# AMC_Connector.net
KiCad netlist of a schematic drawn in Altium Designer
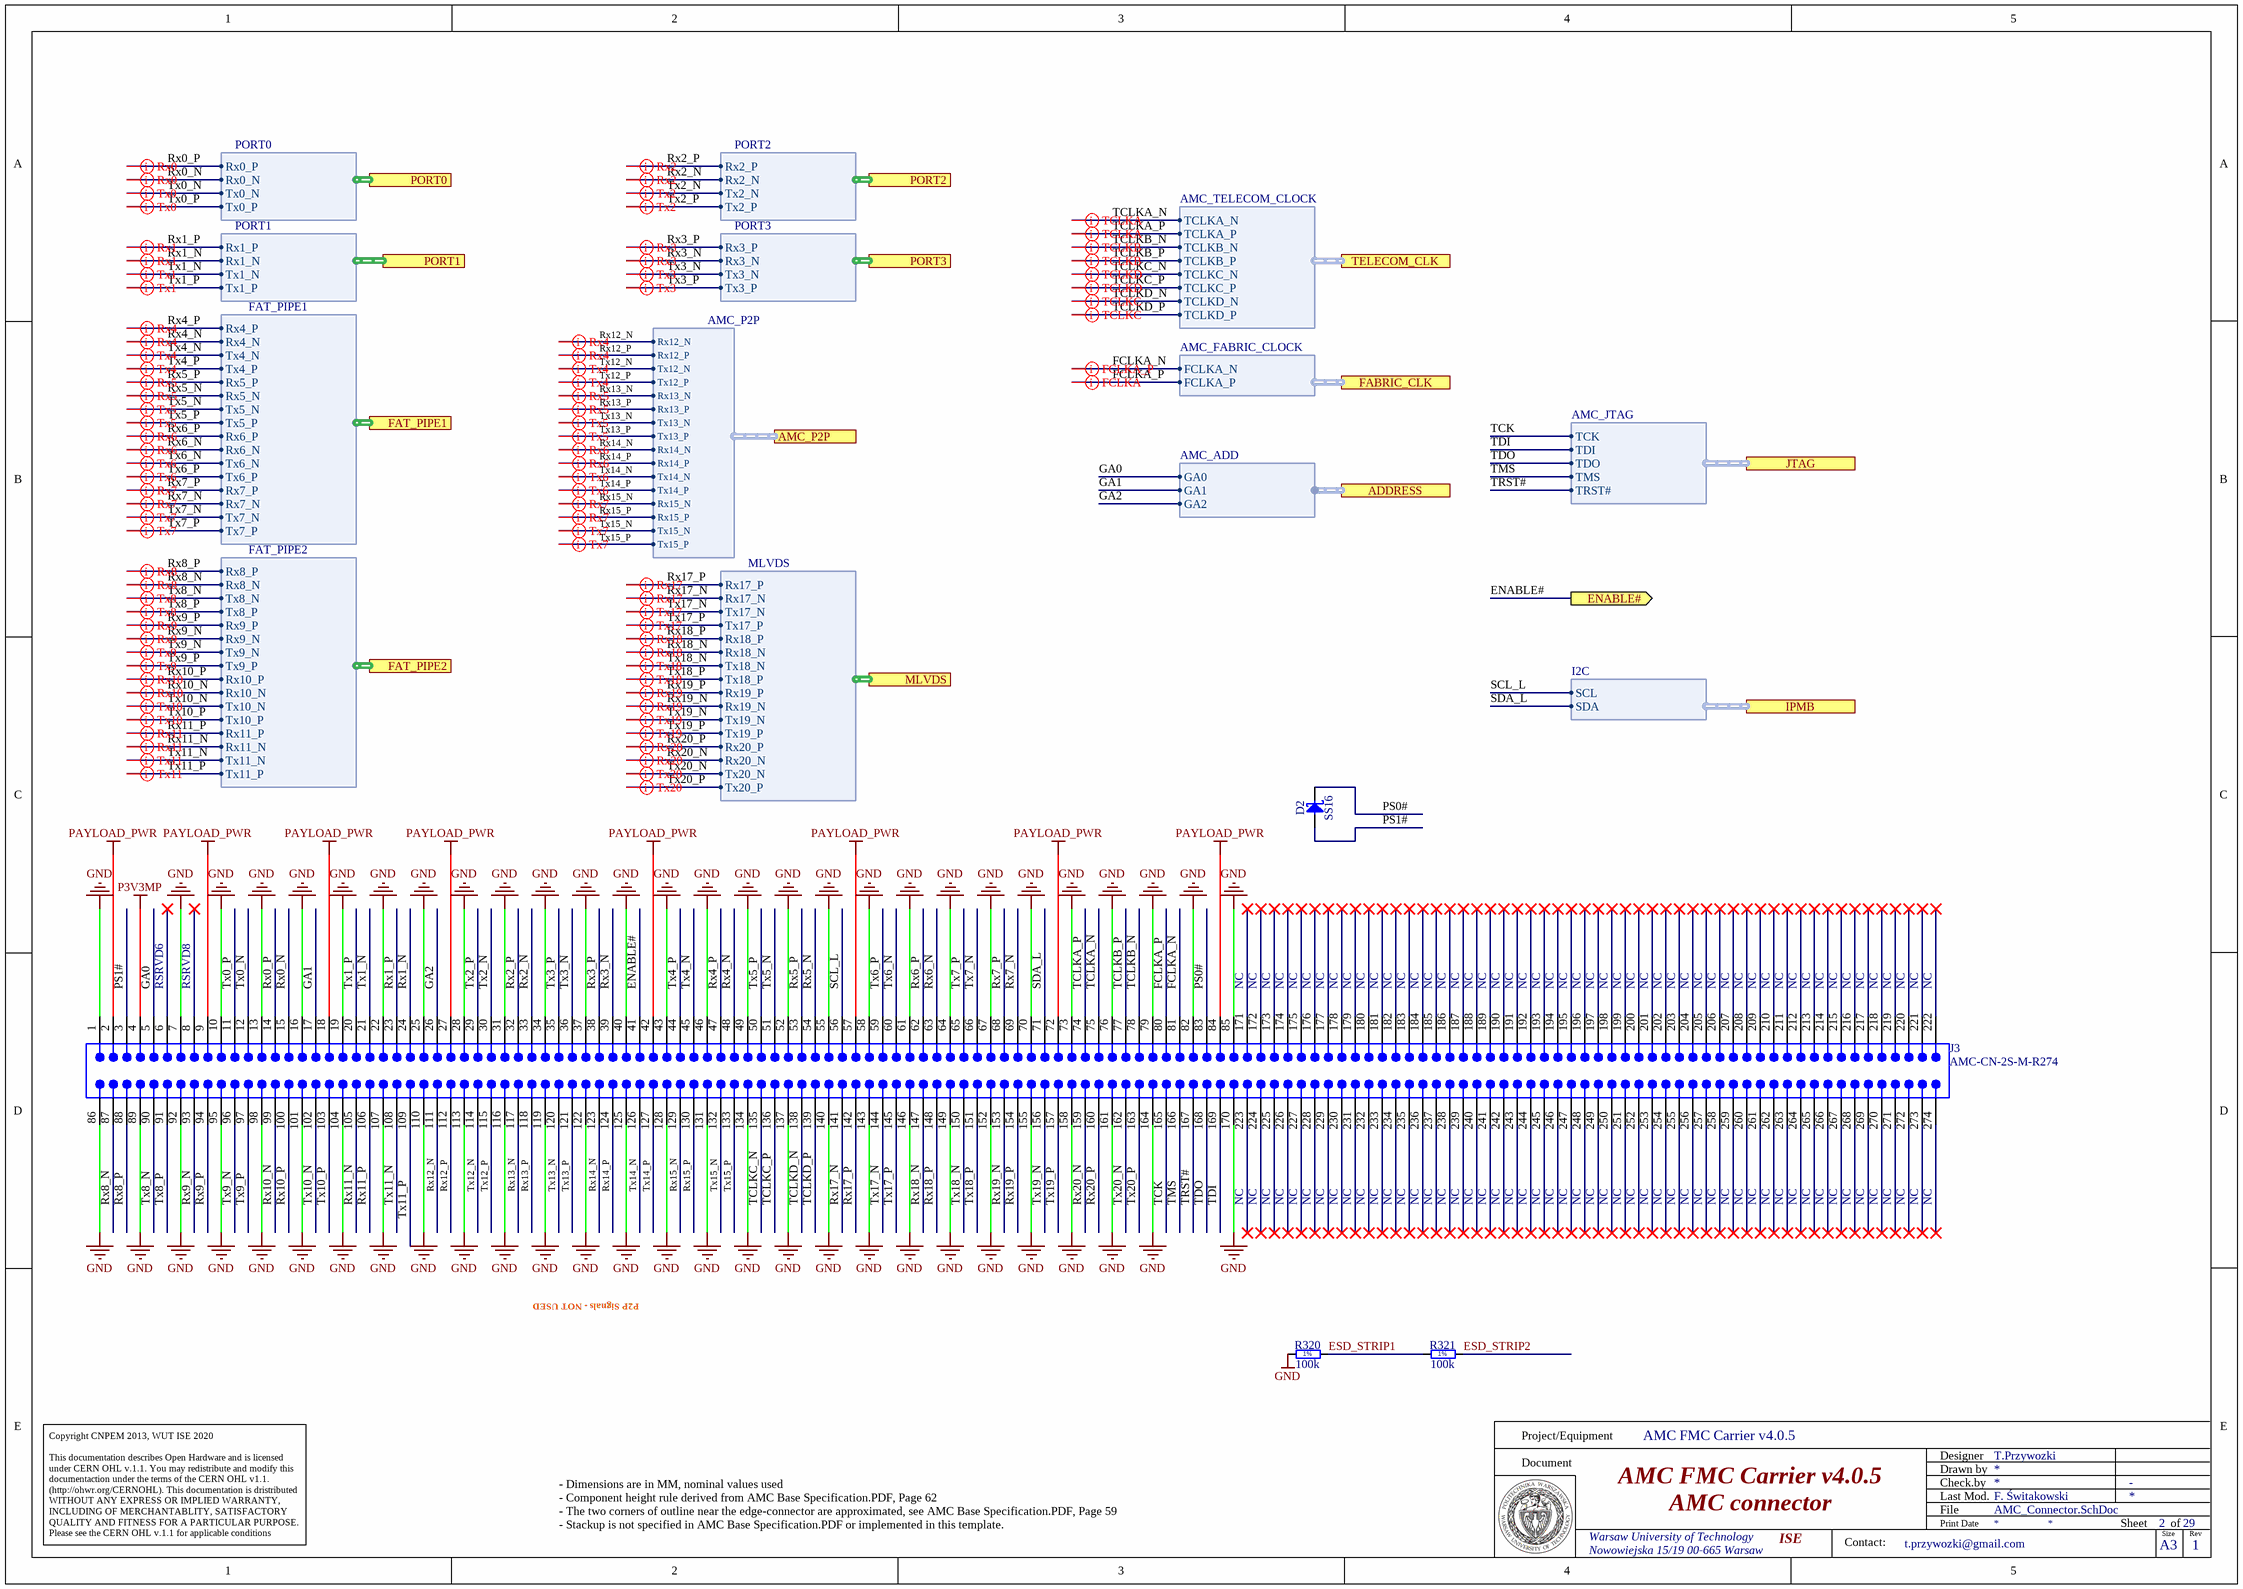
[diagram p0: AMC_Connector.SchDoc]

(export (version "E")
  (design (tool "Eeschema 10.0.6"))
  (components
    (comp (ref "D2")
      (value "SS16")
      (footprint "DIOM5127X229N")
      (description "Schottky Diode")
      (fields
        (field (name "VOLTAGE") "60V")
        (field (name "POWER") "1A")
        (field (name "AUTHOR") "CERN DEM JLC")
      )
      (libsource (lib "ICs And Semiconductors") (part "Diode Schottky"))
    )
    (comp (ref "J3")
      (value "AMC-CN-2S-M-R274")
      (footprint "AMC-GF-2D-750-O274")
      (description "Golden finger, AMC, Dual, Opposite, Pitch 0.75mm, 170-Position")
      (fields (field (name "PUBLISHER") "Altium"))
      (libsource (lib "Altium Shanghai") (part "CMP-0001-00058-2"))
    )
    (comp (ref "R320")
      (value "100k")
      (footprint "RESC3216X65N")
      (description "Resistor - 1%")
      (fields
        (field (name "PART NUMBER") "R1206_100K_1%_0.25W_100PPM")
        (field (name "POWER") "0.25W")
        (field (name "AUTHOR") "CERN DEM JLC")
      )
      (libsource (lib "Resistors") (part "Resistor - 1%"))
    )
    (comp (ref "R321")
      (value "100k")
      (footprint "RESC3216X65N")
      (description "Resistor - 1%")
      (fields
        (field (name "PART NUMBER") "R1206_100K_1%_0.25W_100PPM")
        (field (name "POWER") "0.25W")
        (field (name "AUTHOR") "CERN DEM JLC")
      )
      (libsource (lib "Resistors") (part "Resistor - 1%"))
    )
  )
  (nets
    (net (code "14") (name "/ENABLE#") (class "Default")
      (node (ref "J3") (pin "41") (pinfunction "41_41") (pintype "passive"))
    )
    (net (code "15") (name "/ESD_STRIP1") (class "Default")
      (node (ref "R320") (pin "2") (pinfunction "2_2") (pintype "passive"))
      (node (ref "R321") (pin "1") (pinfunction "1_1") (pintype "passive"))
    )
    (net (code "16") (name "/ESD_STRIP2") (class "Default")
      (node (ref "R321") (pin "2") (pinfunction "2_2") (pintype "passive"))
    )
    (net (code "17") (name "/FCLKA_N") (class "Default")
      (node (ref "J3") (pin "81") (pinfunction "81_81") (pintype "passive"))
    )
    (net (code "18") (name "/FCLKA_P") (class "Default")
      (node (ref "J3") (pin "80") (pinfunction "80_80") (pintype "passive"))
    )
    (net (code "19") (name "/GA0") (class "Default")
      (node (ref "J3") (pin "5") (pinfunction "5_5") (pintype "passive"))
    )
    (net (code "20") (name "/GA1") (class "Default")
      (node (ref "J3") (pin "17") (pinfunction "17_17") (pintype "passive"))
    )
    (net (code "21") (name "/GA2") (class "Default")
      (node (ref "J3") (pin "26") (pinfunction "26_26") (pintype "passive"))
    )
    (net (code "22") (name "/PS0#") (class "Default")
      (node (ref "D2") (pin "1") (pinfunction "C_1") (pintype "passive"))
      (node (ref "J3") (pin "83") (pinfunction "83_83") (pintype "passive"))
    )
    (net (code "23") (name "/PS1#") (class "Default")
      (node (ref "D2") (pin "2") (pinfunction "A_2") (pintype "passive"))
      (node (ref "J3") (pin "3") (pinfunction "3_3") (pintype "passive"))
    )
    (net (code "24") (name "/Rx0_N") (class "Default")
      (node (ref "J3") (pin "15") (pinfunction "15_15") (pintype "passive"))
    )
    (net (code "25") (name "/Rx0_P") (class "Default")
      (node (ref "J3") (pin "14") (pinfunction "14_14") (pintype "passive"))
    )
    (net (code "26") (name "/Rx1_N") (class "Default")
      (node (ref "J3") (pin "24") (pinfunction "24_24") (pintype "passive"))
    )
    (net (code "27") (name "/Rx1_P") (class "Default")
      (node (ref "J3") (pin "23") (pinfunction "23_23") (pintype "passive"))
    )
    (net (code "28") (name "/Rx2_N") (class "Default")
      (node (ref "J3") (pin "33") (pinfunction "33_33") (pintype "passive"))
    )
    (net (code "29") (name "/Rx2_P") (class "Default")
      (node (ref "J3") (pin "32") (pinfunction "32_32") (pintype "passive"))
    )
    (net (code "30") (name "/Rx3_N") (class "Default")
      (node (ref "J3") (pin "39") (pinfunction "39_39") (pintype "passive"))
    )
    (net (code "31") (name "/Rx3_P") (class "Default")
      (node (ref "J3") (pin "38") (pinfunction "38_38") (pintype "passive"))
    )
    (net (code "32") (name "/Rx4_N") (class "Default")
      (node (ref "J3") (pin "48") (pinfunction "48_48") (pintype "passive"))
    )
    (net (code "33") (name "/Rx4_P") (class "Default")
      (node (ref "J3") (pin "47") (pinfunction "47_47") (pintype "passive"))
    )
    (net (code "34") (name "/Rx5_N") (class "Default")
      (node (ref "J3") (pin "54") (pinfunction "54_54") (pintype "passive"))
    )
    (net (code "35") (name "/Rx5_P") (class "Default")
      (node (ref "J3") (pin "53") (pinfunction "53_53") (pintype "passive"))
    )
    (net (code "36") (name "/Rx6_N") (class "Default")
      (node (ref "J3") (pin "63") (pinfunction "63_63") (pintype "passive"))
    )
    (net (code "37") (name "/Rx6_P") (class "Default")
      (node (ref "J3") (pin "62") (pinfunction "62_62") (pintype "passive"))
    )
    (net (code "38") (name "/Rx7_N") (class "Default")
      (node (ref "J3") (pin "69") (pinfunction "69_69") (pintype "passive"))
    )
    (net (code "39") (name "/Rx7_P") (class "Default")
      (node (ref "J3") (pin "68") (pinfunction "68_68") (pintype "passive"))
    )
    (net (code "40") (name "/Rx8_N") (class "Default")
      (node (ref "J3") (pin "87") (pinfunction "87_87") (pintype "passive"))
    )
    (net (code "41") (name "/Rx8_P") (class "Default")
      (node (ref "J3") (pin "88") (pinfunction "88_88") (pintype "passive"))
    )
    (net (code "42") (name "/Rx9_N") (class "Default")
      (node (ref "J3") (pin "93") (pinfunction "93_93") (pintype "passive"))
    )
    (net (code "43") (name "/Rx9_P") (class "Default")
      (node (ref "J3") (pin "94") (pinfunction "94_94") (pintype "passive"))
    )
    (net (code "44") (name "/Rx10_N") (class "Default")
      (node (ref "J3") (pin "99") (pinfunction "99_99") (pintype "passive"))
    )
    (net (code "45") (name "/Rx10_P") (class "Default")
      (node (ref "J3") (pin "100") (pinfunction "100_100") (pintype "passive"))
    )
    (net (code "46") (name "/Rx11_N") (class "Default")
      (node (ref "J3") (pin "105") (pinfunction "105_105") (pintype "passive"))
    )
    (net (code "47") (name "/Rx11_P") (class "Default")
      (node (ref "J3") (pin "106") (pinfunction "106_106") (pintype "passive"))
    )
    (net (code "48") (name "/Rx12_N") (class "Default")
      (node (ref "J3") (pin "111") (pinfunction "111_111") (pintype "passive"))
    )
    (net (code "49") (name "/Rx12_P") (class "Default")
      (node (ref "J3") (pin "112") (pinfunction "112_112") (pintype "passive"))
    )
    (net (code "50") (name "/Rx13_N") (class "Default")
      (node (ref "J3") (pin "117") (pinfunction "117_117") (pintype "passive"))
    )
    (net (code "51") (name "/Rx13_P") (class "Default")
      (node (ref "J3") (pin "118") (pinfunction "118_118") (pintype "passive"))
    )
    (net (code "52") (name "/Rx14_N") (class "Default")
      (node (ref "J3") (pin "123") (pinfunction "123_123") (pintype "passive"))
    )
    (net (code "53") (name "/Rx14_P") (class "Default")
      (node (ref "J3") (pin "124") (pinfunction "124_124") (pintype "passive"))
    )
    (net (code "54") (name "/Rx15_N") (class "Default")
      (node (ref "J3") (pin "129") (pinfunction "129_129") (pintype "passive"))
    )
    (net (code "55") (name "/Rx15_P") (class "Default")
      (node (ref "J3") (pin "130") (pinfunction "130_130") (pintype "passive"))
    )
    (net (code "56") (name "/Rx17_N") (class "Default")
      (node (ref "J3") (pin "141") (pinfunction "141_141") (pintype "passive"))
    )
    (net (code "57") (name "/Rx17_P") (class "Default")
      (node (ref "J3") (pin "142") (pinfunction "142_142") (pintype "passive"))
    )
    (net (code "58") (name "/Rx18_N") (class "Default")
      (node (ref "J3") (pin "147") (pinfunction "147_147") (pintype "passive"))
    )
    (net (code "59") (name "/Rx18_P") (class "Default")
      (node (ref "J3") (pin "148") (pinfunction "148_148") (pintype "passive"))
    )
    (net (code "60") (name "/Rx19_N") (class "Default")
      (node (ref "J3") (pin "153") (pinfunction "153_153") (pintype "passive"))
    )
    (net (code "61") (name "/Rx19_P") (class "Default")
      (node (ref "J3") (pin "154") (pinfunction "154_154") (pintype "passive"))
    )
    (net (code "62") (name "/Rx20_N") (class "Default")
      (node (ref "J3") (pin "159") (pinfunction "159_159") (pintype "passive"))
    )
    (net (code "63") (name "/Rx20_P") (class "Default")
      (node (ref "J3") (pin "160") (pinfunction "160_160") (pintype "passive"))
    )
    (net (code "64") (name "/SCL_L") (class "Default")
      (node (ref "J3") (pin "56") (pinfunction "56_56") (pintype "passive"))
    )
    (net (code "65") (name "/SDA_L") (class "Default")
      (node (ref "J3") (pin "71") (pinfunction "71_71") (pintype "passive"))
    )
    (net (code "66") (name "/TCK") (class "Default")
      (node (ref "J3") (pin "165") (pinfunction "165_165") (pintype "passive"))
    )
    (net (code "67") (name "/TCLKA_N") (class "Default")
      (node (ref "J3") (pin "75") (pinfunction "75_75") (pintype "passive"))
    )
    (net (code "68") (name "/TCLKA_P") (class "Default")
      (node (ref "J3") (pin "74") (pinfunction "74_74") (pintype "passive"))
    )
    (net (code "69") (name "/TCLKB_N") (class "Default")
      (node (ref "J3") (pin "78") (pinfunction "78_78") (pintype "passive"))
    )
    (net (code "70") (name "/TCLKB_P") (class "Default")
      (node (ref "J3") (pin "77") (pinfunction "77_77") (pintype "passive"))
    )
    (net (code "71") (name "/TCLKC_N") (class "Default")
      (node (ref "J3") (pin "135") (pinfunction "135_135") (pintype "passive"))
    )
    (net (code "72") (name "/TCLKC_P") (class "Default")
      (node (ref "J3") (pin "136") (pinfunction "136_136") (pintype "passive"))
    )
    (net (code "73") (name "/TCLKD_N") (class "Default")
      (node (ref "J3") (pin "138") (pinfunction "138_138") (pintype "passive"))
    )
    (net (code "74") (name "/TCLKD_P") (class "Default")
      (node (ref "J3") (pin "139") (pinfunction "139_139") (pintype "passive"))
    )
    (net (code "75") (name "/TDI") (class "Default")
      (node (ref "J3") (pin "169") (pinfunction "169_169") (pintype "passive"))
    )
    (net (code "76") (name "/TDO") (class "Default")
      (node (ref "J3") (pin "168") (pinfunction "168_168") (pintype "passive"))
    )
    (net (code "77") (name "/TMS") (class "Default")
      (node (ref "J3") (pin "166") (pinfunction "166_166") (pintype "passive"))
    )
    (net (code "78") (name "/TRST#") (class "Default")
      (node (ref "J3") (pin "167") (pinfunction "167_167") (pintype "passive"))
    )
    (net (code "79") (name "/Tx0_N") (class "Default")
      (node (ref "J3") (pin "12") (pinfunction "12_12") (pintype "passive"))
    )
    (net (code "80") (name "/Tx0_P") (class "Default")
      (node (ref "J3") (pin "11") (pinfunction "11_11") (pintype "passive"))
    )
    (net (code "81") (name "/Tx1_N") (class "Default")
      (node (ref "J3") (pin "21") (pinfunction "21_21") (pintype "passive"))
    )
    (net (code "82") (name "/Tx1_P") (class "Default")
      (node (ref "J3") (pin "20") (pinfunction "20_20") (pintype "passive"))
    )
    (net (code "83") (name "/Tx2_N") (class "Default")
      (node (ref "J3") (pin "30") (pinfunction "30_30") (pintype "passive"))
    )
    (net (code "84") (name "/Tx2_P") (class "Default")
      (node (ref "J3") (pin "29") (pinfunction "29_29") (pintype "passive"))
    )
    (net (code "85") (name "/Tx3_N") (class "Default")
      (node (ref "J3") (pin "36") (pinfunction "36_36") (pintype "passive"))
    )
    (net (code "86") (name "/Tx3_P") (class "Default")
      (node (ref "J3") (pin "35") (pinfunction "35_35") (pintype "passive"))
    )
    (net (code "87") (name "/Tx4_N") (class "Default")
      (node (ref "J3") (pin "45") (pinfunction "45_45") (pintype "passive"))
    )
    (net (code "88") (name "/Tx4_P") (class "Default")
      (node (ref "J3") (pin "44") (pinfunction "44_44") (pintype "passive"))
    )
    (net (code "89") (name "/Tx5_N") (class "Default")
      (node (ref "J3") (pin "51") (pinfunction "51_51") (pintype "passive"))
    )
    (net (code "90") (name "/Tx5_P") (class "Default")
      (node (ref "J3") (pin "50") (pinfunction "50_50") (pintype "passive"))
    )
    (net (code "91") (name "/Tx6_N") (class "Default")
      (node (ref "J3") (pin "60") (pinfunction "60_60") (pintype "passive"))
    )
    (net (code "92") (name "/Tx6_P") (class "Default")
      (node (ref "J3") (pin "59") (pinfunction "59_59") (pintype "passive"))
    )
    (net (code "93") (name "/Tx7_N") (class "Default")
      (node (ref "J3") (pin "66") (pinfunction "66_66") (pintype "passive"))
    )
    (net (code "94") (name "/Tx7_P") (class "Default")
      (node (ref "J3") (pin "65") (pinfunction "65_65") (pintype "passive"))
    )
    (net (code "95") (name "/Tx8_N") (class "Default")
      (node (ref "J3") (pin "90") (pinfunction "90_90") (pintype "passive"))
    )
    (net (code "96") (name "/Tx8_P") (class "Default")
      (node (ref "J3") (pin "91") (pinfunction "91_91") (pintype "passive"))
    )
    (net (code "97") (name "/Tx9_N") (class "Default")
      (node (ref "J3") (pin "96") (pinfunction "96_96") (pintype "passive"))
    )
    (net (code "98") (name "/Tx9_P") (class "Default")
      (node (ref "J3") (pin "97") (pinfunction "97_97") (pintype "passive"))
    )
    (net (code "99") (name "/Tx10_N") (class "Default")
      (node (ref "J3") (pin "102") (pinfunction "102_102") (pintype "passive"))
    )
    (net (code "100") (name "/Tx10_P") (class "Default")
      (node (ref "J3") (pin "103") (pinfunction "103_103") (pintype "passive"))
    )
    (net (code "101") (name "/Tx11_N") (class "Default")
      (node (ref "J3") (pin "108") (pinfunction "108_108") (pintype "passive"))
    )
    (net (code "102") (name "/Tx11_P") (class "Default")
      (node (ref "J3") (pin "109") (pinfunction "109_109") (pintype "passive"))
    )
    (net (code "103") (name "/Tx12_N") (class "Default")
      (node (ref "J3") (pin "114") (pinfunction "114_114") (pintype "passive"))
    )
    (net (code "104") (name "/Tx12_P") (class "Default")
      (node (ref "J3") (pin "115") (pinfunction "115_115") (pintype "passive"))
    )
    (net (code "105") (name "/Tx13_N") (class "Default")
      (node (ref "J3") (pin "120") (pinfunction "120_120") (pintype "passive"))
    )
    (net (code "106") (name "/Tx13_P") (class "Default")
      (node (ref "J3") (pin "121") (pinfunction "121_121") (pintype "passive"))
    )
    (net (code "107") (name "/Tx14_N") (class "Default")
      (node (ref "J3") (pin "126") (pinfunction "126_126") (pintype "passive"))
    )
    (net (code "108") (name "/Tx14_P") (class "Default")
      (node (ref "J3") (pin "127") (pinfunction "127_127") (pintype "passive"))
    )
    (net (code "109") (name "/Tx15_N") (class "Default")
      (node (ref "J3") (pin "132") (pinfunction "132_132") (pintype "passive"))
    )
    (net (code "110") (name "/Tx15_P") (class "Default")
      (node (ref "J3") (pin "133") (pinfunction "133_133") (pintype "passive"))
    )
    (net (code "111") (name "/Tx17_N") (class "Default")
      (node (ref "J3") (pin "144") (pinfunction "144_144") (pintype "passive"))
    )
    (net (code "112") (name "/Tx17_P") (class "Default")
      (node (ref "J3") (pin "145") (pinfunction "145_145") (pintype "passive"))
    )
    (net (code "113") (name "/Tx18_N") (class "Default")
      (node (ref "J3") (pin "150") (pinfunction "150_150") (pintype "passive"))
    )
    (net (code "114") (name "/Tx18_P") (class "Default")
      (node (ref "J3") (pin "151") (pinfunction "151_151") (pintype "passive"))
    )
    (net (code "115") (name "/Tx19_N") (class "Default")
      (node (ref "J3") (pin "156") (pinfunction "156_156") (pintype "passive"))
    )
    (net (code "116") (name "/Tx19_P") (class "Default")
      (node (ref "J3") (pin "157") (pinfunction "157_157") (pintype "passive"))
    )
    (net (code "117") (name "/Tx20_N") (class "Default")
      (node (ref "J3") (pin "162") (pinfunction "162_162") (pintype "passive"))
    )
    (net (code "118") (name "/Tx20_P") (class "Default")
      (node (ref "J3") (pin "163") (pinfunction "163_163") (pintype "passive"))
    )
    (net (code "132") (name "GND") (class "Default")
      (node (ref "J3") (pin "1") (pinfunction "1_1") (pintype "passive"))
      (node (ref "J3") (pin "10") (pinfunction "10_10") (pintype "passive"))
      (node (ref "J3") (pin "101") (pinfunction "101_101") (pintype "passive"))
      (node (ref "J3") (pin "104") (pinfunction "104_104") (pintype "passive"))
      (node (ref "J3") (pin "107") (pinfunction "107_107") (pintype "passive"))
      (node (ref "J3") (pin "110") (pinfunction "110_110") (pintype "passive"))
      (node (ref "J3") (pin "113") (pinfunction "113_113") (pintype "passive"))
      (node (ref "J3") (pin "116") (pinfunction "116_116") (pintype "passive"))
      (node (ref "J3") (pin "119") (pinfunction "119_119") (pintype "passive"))
      (node (ref "J3") (pin "122") (pinfunction "122_122") (pintype "passive"))
      (node (ref "J3") (pin "125") (pinfunction "125_125") (pintype "passive"))
      (node (ref "J3") (pin "128") (pinfunction "128_128") (pintype "passive"))
      (node (ref "J3") (pin "13") (pinfunction "13_13") (pintype "passive"))
      (node (ref "J3") (pin "131") (pinfunction "131_131") (pintype "passive"))
      (node (ref "J3") (pin "134") (pinfunction "134_134") (pintype "passive"))
      (node (ref "J3") (pin "137") (pinfunction "137_137") (pintype "passive"))
      (node (ref "J3") (pin "140") (pinfunction "140_140") (pintype "passive"))
      (node (ref "J3") (pin "143") (pinfunction "143_143") (pintype "passive"))
      (node (ref "J3") (pin "146") (pinfunction "146_146") (pintype "passive"))
      (node (ref "J3") (pin "149") (pinfunction "149_149") (pintype "passive"))
      (node (ref "J3") (pin "152") (pinfunction "152_152") (pintype "passive"))
      (node (ref "J3") (pin "155") (pinfunction "155_155") (pintype "passive"))
      (node (ref "J3") (pin "158") (pinfunction "158_158") (pintype "passive"))
      (node (ref "J3") (pin "16") (pinfunction "16_16") (pintype "passive"))
      (node (ref "J3") (pin "161") (pinfunction "161_161") (pintype "passive"))
      (node (ref "J3") (pin "164") (pinfunction "164_164") (pintype "passive"))
      (node (ref "J3") (pin "170") (pinfunction "170_170") (pintype "passive"))
      (node (ref "J3") (pin "19") (pinfunction "19_19") (pintype "passive"))
      (node (ref "J3") (pin "22") (pinfunction "22_22") (pintype "passive"))
      (node (ref "J3") (pin "25") (pinfunction "25_25") (pintype "passive"))
      (node (ref "J3") (pin "28") (pinfunction "28_28") (pintype "passive"))
      (node (ref "J3") (pin "31") (pinfunction "31_31") (pintype "passive"))
      (node (ref "J3") (pin "34") (pinfunction "34_34") (pintype "passive"))
      (node (ref "J3") (pin "37") (pinfunction "37_37") (pintype "passive"))
      (node (ref "J3") (pin "40") (pinfunction "40_40") (pintype "passive"))
      (node (ref "J3") (pin "43") (pinfunction "43_43") (pintype "passive"))
      (node (ref "J3") (pin "46") (pinfunction "46_46") (pintype "passive"))
      (node (ref "J3") (pin "49") (pinfunction "49_49") (pintype "passive"))
      (node (ref "J3") (pin "52") (pinfunction "52_52") (pintype "passive"))
      (node (ref "J3") (pin "55") (pinfunction "55_55") (pintype "passive"))
      (node (ref "J3") (pin "58") (pinfunction "58_58") (pintype "passive"))
      (node (ref "J3") (pin "61") (pinfunction "61_61") (pintype "passive"))
      (node (ref "J3") (pin "64") (pinfunction "64_64") (pintype "passive"))
      (node (ref "J3") (pin "67") (pinfunction "67_67") (pintype "passive"))
      (node (ref "J3") (pin "7") (pinfunction "7_7") (pintype "passive"))
      (node (ref "J3") (pin "70") (pinfunction "70_70") (pintype "passive"))
      (node (ref "J3") (pin "73") (pinfunction "73_73") (pintype "passive"))
      (node (ref "J3") (pin "76") (pinfunction "76_76") (pintype "passive"))
      (node (ref "J3") (pin "79") (pinfunction "79_79") (pintype "passive"))
      (node (ref "J3") (pin "82") (pinfunction "82_82") (pintype "passive"))
      (node (ref "J3") (pin "85") (pinfunction "85_85") (pintype "passive"))
      (node (ref "J3") (pin "86") (pinfunction "86_86") (pintype "passive"))
      (node (ref "J3") (pin "89") (pinfunction "89_89") (pintype "passive"))
      (node (ref "J3") (pin "92") (pinfunction "92_92") (pintype "passive"))
      (node (ref "J3") (pin "95") (pinfunction "95_95") (pintype "passive"))
      (node (ref "J3") (pin "98") (pinfunction "98_98") (pintype "passive"))
      (node (ref "R320") (pin "1") (pinfunction "1_1") (pintype "passive"))
    )
    (net (code "133") (name "P3V3MP") (class "Default")
      (node (ref "J3") (pin "4") (pinfunction "4_4") (pintype "passive"))
    )
    (net (code "134") (name "PAYLOAD_PWR") (class "Default")
      (node (ref "J3") (pin "18") (pinfunction "18_18") (pintype "passive"))
      (node (ref "J3") (pin "2") (pinfunction "2_2") (pintype "passive"))
      (node (ref "J3") (pin "27") (pinfunction "27_27") (pintype "passive"))
      (node (ref "J3") (pin "42") (pinfunction "42_42") (pintype "passive"))
      (node (ref "J3") (pin "57") (pinfunction "57_57") (pintype "passive"))
      (node (ref "J3") (pin "72") (pinfunction "72_72") (pintype "passive"))
      (node (ref "J3") (pin "84") (pinfunction "84_84") (pintype "passive"))
      (node (ref "J3") (pin "9") (pinfunction "9_9") (pintype "passive"))
    )
    (net (code "135") (name "unconnected-(J3-Pad6)") (class "Default")
      (node (ref "J3") (pin "6") (pinfunction "6_6") (pintype "passive+no_connect"))
    )
    (net (code "136") (name "unconnected-(J3-Pad8)") (class "Default")
      (node (ref "J3") (pin "8") (pinfunction "8_8") (pintype "passive+no_connect"))
    )
    (net (code "137") (name "unconnected-(J3-Pad171)") (class "Default")
      (node (ref "J3") (pin "171") (pinfunction "171_171") (pintype "passive+no_connect"))
    )
    (net (code "138") (name "unconnected-(J3-Pad172)") (class "Default")
      (node (ref "J3") (pin "172") (pinfunction "172_172") (pintype "passive+no_connect"))
    )
    (net (code "139") (name "unconnected-(J3-Pad173)") (class "Default")
      (node (ref "J3") (pin "173") (pinfunction "173_173") (pintype "passive+no_connect"))
    )
    (net (code "140") (name "unconnected-(J3-Pad174)") (class "Default")
      (node (ref "J3") (pin "174") (pinfunction "174_174") (pintype "passive+no_connect"))
    )
    (net (code "141") (name "unconnected-(J3-Pad175)") (class "Default")
      (node (ref "J3") (pin "175") (pinfunction "175_175") (pintype "passive+no_connect"))
    )
    (net (code "142") (name "unconnected-(J3-Pad176)") (class "Default")
      (node (ref "J3") (pin "176") (pinfunction "176_176") (pintype "passive+no_connect"))
    )
    (net (code "143") (name "unconnected-(J3-Pad177)") (class "Default")
      (node (ref "J3") (pin "177") (pinfunction "177_177") (pintype "passive+no_connect"))
    )
    (net (code "144") (name "unconnected-(J3-Pad178)") (class "Default")
      (node (ref "J3") (pin "178") (pinfunction "178_178") (pintype "passive+no_connect"))
    )
    (net (code "145") (name "unconnected-(J3-Pad179)") (class "Default")
      (node (ref "J3") (pin "179") (pinfunction "179_179") (pintype "passive+no_connect"))
    )
    (net (code "146") (name "unconnected-(J3-Pad180)") (class "Default")
      (node (ref "J3") (pin "180") (pinfunction "180_180") (pintype "passive+no_connect"))
    )
    (net (code "147") (name "unconnected-(J3-Pad181)") (class "Default")
      (node (ref "J3") (pin "181") (pinfunction "181_181") (pintype "passive+no_connect"))
    )
    (net (code "148") (name "unconnected-(J3-Pad182)") (class "Default")
      (node (ref "J3") (pin "182") (pinfunction "182_182") (pintype "passive+no_connect"))
    )
    (net (code "149") (name "unconnected-(J3-Pad183)") (class "Default")
      (node (ref "J3") (pin "183") (pinfunction "183_183") (pintype "passive+no_connect"))
    )
    (net (code "150") (name "unconnected-(J3-Pad184)") (class "Default")
      (node (ref "J3") (pin "184") (pinfunction "184_184") (pintype "passive+no_connect"))
    )
    (net (code "151") (name "unconnected-(J3-Pad185)") (class "Default")
      (node (ref "J3") (pin "185") (pinfunction "185_185") (pintype "passive+no_connect"))
    )
    (net (code "152") (name "unconnected-(J3-Pad186)") (class "Default")
      (node (ref "J3") (pin "186") (pinfunction "186_186") (pintype "passive+no_connect"))
    )
    (net (code "153") (name "unconnected-(J3-Pad187)") (class "Default")
      (node (ref "J3") (pin "187") (pinfunction "187_187") (pintype "passive+no_connect"))
    )
    (net (code "154") (name "unconnected-(J3-Pad188)") (class "Default")
      (node (ref "J3") (pin "188") (pinfunction "188_188") (pintype "passive+no_connect"))
    )
    (net (code "155") (name "unconnected-(J3-Pad189)") (class "Default")
      (node (ref "J3") (pin "189") (pinfunction "189_189") (pintype "passive+no_connect"))
    )
    (net (code "156") (name "unconnected-(J3-Pad190)") (class "Default")
      (node (ref "J3") (pin "190") (pinfunction "190_190") (pintype "passive+no_connect"))
    )
    (net (code "157") (name "unconnected-(J3-Pad191)") (class "Default")
      (node (ref "J3") (pin "191") (pinfunction "191_191") (pintype "passive+no_connect"))
    )
    (net (code "158") (name "unconnected-(J3-Pad192)") (class "Default")
      (node (ref "J3") (pin "192") (pinfunction "192_192") (pintype "passive+no_connect"))
    )
    (net (code "159") (name "unconnected-(J3-Pad193)") (class "Default")
      (node (ref "J3") (pin "193") (pinfunction "193_193") (pintype "passive+no_connect"))
    )
    (net (code "160") (name "unconnected-(J3-Pad194)") (class "Default")
      (node (ref "J3") (pin "194") (pinfunction "194_194") (pintype "passive+no_connect"))
    )
    (net (code "161") (name "unconnected-(J3-Pad195)") (class "Default")
      (node (ref "J3") (pin "195") (pinfunction "195_195") (pintype "passive+no_connect"))
    )
    (net (code "162") (name "unconnected-(J3-Pad196)") (class "Default")
      (node (ref "J3") (pin "196") (pinfunction "196_196") (pintype "passive+no_connect"))
    )
    (net (code "163") (name "unconnected-(J3-Pad197)") (class "Default")
      (node (ref "J3") (pin "197") (pinfunction "197_197") (pintype "passive+no_connect"))
    )
    (net (code "164") (name "unconnected-(J3-Pad198)") (class "Default")
      (node (ref "J3") (pin "198") (pinfunction "198_198") (pintype "passive+no_connect"))
    )
    (net (code "165") (name "unconnected-(J3-Pad199)") (class "Default")
      (node (ref "J3") (pin "199") (pinfunction "199_199") (pintype "passive+no_connect"))
    )
    (net (code "166") (name "unconnected-(J3-Pad200)") (class "Default")
      (node (ref "J3") (pin "200") (pinfunction "200_200") (pintype "passive+no_connect"))
    )
    (net (code "167") (name "unconnected-(J3-Pad201)") (class "Default")
      (node (ref "J3") (pin "201") (pinfunction "201_201") (pintype "passive+no_connect"))
    )
    (net (code "168") (name "unconnected-(J3-Pad202)") (class "Default")
      (node (ref "J3") (pin "202") (pinfunction "202_202") (pintype "passive+no_connect"))
    )
    (net (code "169") (name "unconnected-(J3-Pad203)") (class "Default")
      (node (ref "J3") (pin "203") (pinfunction "203_203") (pintype "passive+no_connect"))
    )
    (net (code "170") (name "unconnected-(J3-Pad204)") (class "Default")
      (node (ref "J3") (pin "204") (pinfunction "204_204") (pintype "passive+no_connect"))
    )
    (net (code "171") (name "unconnected-(J3-Pad205)") (class "Default")
      (node (ref "J3") (pin "205") (pinfunction "205_205") (pintype "passive+no_connect"))
    )
    (net (code "172") (name "unconnected-(J3-Pad206)") (class "Default")
      (node (ref "J3") (pin "206") (pinfunction "206_206") (pintype "passive+no_connect"))
    )
    (net (code "173") (name "unconnected-(J3-Pad207)") (class "Default")
      (node (ref "J3") (pin "207") (pinfunction "207_207") (pintype "passive+no_connect"))
    )
    (net (code "174") (name "unconnected-(J3-Pad208)") (class "Default")
      (node (ref "J3") (pin "208") (pinfunction "208_208") (pintype "passive+no_connect"))
    )
    (net (code "175") (name "unconnected-(J3-Pad209)") (class "Default")
      (node (ref "J3") (pin "209") (pinfunction "209_209") (pintype "passive+no_connect"))
    )
    (net (code "176") (name "unconnected-(J3-Pad210)") (class "Default")
      (node (ref "J3") (pin "210") (pinfunction "210_210") (pintype "passive+no_connect"))
    )
    (net (code "177") (name "unconnected-(J3-Pad211)") (class "Default")
      (node (ref "J3") (pin "211") (pinfunction "211_211") (pintype "passive+no_connect"))
    )
    (net (code "178") (name "unconnected-(J3-Pad212)") (class "Default")
      (node (ref "J3") (pin "212") (pinfunction "212_212") (pintype "passive+no_connect"))
    )
    (net (code "179") (name "unconnected-(J3-Pad213)") (class "Default")
      (node (ref "J3") (pin "213") (pinfunction "213_213") (pintype "passive+no_connect"))
    )
    (net (code "180") (name "unconnected-(J3-Pad214)") (class "Default")
      (node (ref "J3") (pin "214") (pinfunction "214_214") (pintype "passive+no_connect"))
    )
    (net (code "181") (name "unconnected-(J3-Pad215)") (class "Default")
      (node (ref "J3") (pin "215") (pinfunction "215_215") (pintype "passive+no_connect"))
    )
    (net (code "182") (name "unconnected-(J3-Pad216)") (class "Default")
      (node (ref "J3") (pin "216") (pinfunction "216_216") (pintype "passive+no_connect"))
    )
    (net (code "183") (name "unconnected-(J3-Pad217)") (class "Default")
      (node (ref "J3") (pin "217") (pinfunction "217_217") (pintype "passive+no_connect"))
    )
    (net (code "184") (name "unconnected-(J3-Pad218)") (class "Default")
      (node (ref "J3") (pin "218") (pinfunction "218_218") (pintype "passive+no_connect"))
    )
    (net (code "185") (name "unconnected-(J3-Pad219)") (class "Default")
      (node (ref "J3") (pin "219") (pinfunction "219_219") (pintype "passive+no_connect"))
    )
    (net (code "186") (name "unconnected-(J3-Pad220)") (class "Default")
      (node (ref "J3") (pin "220") (pinfunction "220_220") (pintype "passive+no_connect"))
    )
    (net (code "187") (name "unconnected-(J3-Pad221)") (class "Default")
      (node (ref "J3") (pin "221") (pinfunction "221_221") (pintype "passive+no_connect"))
    )
    (net (code "188") (name "unconnected-(J3-Pad222)") (class "Default")
      (node (ref "J3") (pin "222") (pinfunction "222_222") (pintype "passive+no_connect"))
    )
    (net (code "189") (name "unconnected-(J3-Pad223)") (class "Default")
      (node (ref "J3") (pin "223") (pinfunction "223_223") (pintype "passive+no_connect"))
    )
    (net (code "190") (name "unconnected-(J3-Pad224)") (class "Default")
      (node (ref "J3") (pin "224") (pinfunction "224_224") (pintype "passive+no_connect"))
    )
    (net (code "191") (name "unconnected-(J3-Pad225)") (class "Default")
      (node (ref "J3") (pin "225") (pinfunction "225_225") (pintype "passive+no_connect"))
    )
    (net (code "192") (name "unconnected-(J3-Pad226)") (class "Default")
      (node (ref "J3") (pin "226") (pinfunction "226_226") (pintype "passive+no_connect"))
    )
    (net (code "193") (name "unconnected-(J3-Pad227)") (class "Default")
      (node (ref "J3") (pin "227") (pinfunction "227_227") (pintype "passive+no_connect"))
    )
    (net (code "194") (name "unconnected-(J3-Pad228)") (class "Default")
      (node (ref "J3") (pin "228") (pinfunction "228_228") (pintype "passive+no_connect"))
    )
    (net (code "195") (name "unconnected-(J3-Pad229)") (class "Default")
      (node (ref "J3") (pin "229") (pinfunction "229_229") (pintype "passive+no_connect"))
    )
    (net (code "196") (name "unconnected-(J3-Pad230)") (class "Default")
      (node (ref "J3") (pin "230") (pinfunction "230_230") (pintype "passive+no_connect"))
    )
    (net (code "197") (name "unconnected-(J3-Pad231)") (class "Default")
      (node (ref "J3") (pin "231") (pinfunction "231_231") (pintype "passive+no_connect"))
    )
    (net (code "198") (name "unconnected-(J3-Pad232)") (class "Default")
      (node (ref "J3") (pin "232") (pinfunction "232_232") (pintype "passive+no_connect"))
    )
    (net (code "199") (name "unconnected-(J3-Pad233)") (class "Default")
      (node (ref "J3") (pin "233") (pinfunction "233_233") (pintype "passive+no_connect"))
    )
    (net (code "200") (name "unconnected-(J3-Pad234)") (class "Default")
      (node (ref "J3") (pin "234") (pinfunction "234_234") (pintype "passive+no_connect"))
    )
    (net (code "201") (name "unconnected-(J3-Pad235)") (class "Default")
      (node (ref "J3") (pin "235") (pinfunction "235_235") (pintype "passive+no_connect"))
    )
    (net (code "202") (name "unconnected-(J3-Pad236)") (class "Default")
      (node (ref "J3") (pin "236") (pinfunction "236_236") (pintype "passive+no_connect"))
    )
    (net (code "203") (name "unconnected-(J3-Pad237)") (class "Default")
      (node (ref "J3") (pin "237") (pinfunction "237_237") (pintype "passive+no_connect"))
    )
    (net (code "204") (name "unconnected-(J3-Pad238)") (class "Default")
      (node (ref "J3") (pin "238") (pinfunction "238_238") (pintype "passive+no_connect"))
    )
    (net (code "205") (name "unconnected-(J3-Pad239)") (class "Default")
      (node (ref "J3") (pin "239") (pinfunction "239_239") (pintype "passive+no_connect"))
    )
    (net (code "206") (name "unconnected-(J3-Pad240)") (class "Default")
      (node (ref "J3") (pin "240") (pinfunction "240_240") (pintype "passive+no_connect"))
    )
    (net (code "207") (name "unconnected-(J3-Pad241)") (class "Default")
      (node (ref "J3") (pin "241") (pinfunction "241_241") (pintype "passive+no_connect"))
    )
    (net (code "208") (name "unconnected-(J3-Pad242)") (class "Default")
      (node (ref "J3") (pin "242") (pinfunction "242_242") (pintype "passive+no_connect"))
    )
    (net (code "209") (name "unconnected-(J3-Pad243)") (class "Default")
      (node (ref "J3") (pin "243") (pinfunction "243_243") (pintype "passive+no_connect"))
    )
    (net (code "210") (name "unconnected-(J3-Pad244)") (class "Default")
      (node (ref "J3") (pin "244") (pinfunction "244_244") (pintype "passive+no_connect"))
    )
    (net (code "211") (name "unconnected-(J3-Pad245)") (class "Default")
      (node (ref "J3") (pin "245") (pinfunction "245_245") (pintype "passive+no_connect"))
    )
    (net (code "212") (name "unconnected-(J3-Pad246)") (class "Default")
      (node (ref "J3") (pin "246") (pinfunction "246_246") (pintype "passive+no_connect"))
    )
    (net (code "213") (name "unconnected-(J3-Pad247)") (class "Default")
      (node (ref "J3") (pin "247") (pinfunction "247_247") (pintype "passive+no_connect"))
    )
    (net (code "214") (name "unconnected-(J3-Pad248)") (class "Default")
      (node (ref "J3") (pin "248") (pinfunction "248_248") (pintype "passive+no_connect"))
    )
    (net (code "215") (name "unconnected-(J3-Pad249)") (class "Default")
      (node (ref "J3") (pin "249") (pinfunction "249_249") (pintype "passive+no_connect"))
    )
    (net (code "216") (name "unconnected-(J3-Pad250)") (class "Default")
      (node (ref "J3") (pin "250") (pinfunction "250_250") (pintype "passive+no_connect"))
    )
    (net (code "217") (name "unconnected-(J3-Pad251)") (class "Default")
      (node (ref "J3") (pin "251") (pinfunction "251_251") (pintype "passive+no_connect"))
    )
    (net (code "218") (name "unconnected-(J3-Pad252)") (class "Default")
      (node (ref "J3") (pin "252") (pinfunction "252_252") (pintype "passive+no_connect"))
    )
    (net (code "219") (name "unconnected-(J3-Pad253)") (class "Default")
      (node (ref "J3") (pin "253") (pinfunction "253_253") (pintype "passive+no_connect"))
    )
    (net (code "220") (name "unconnected-(J3-Pad254)") (class "Default")
      (node (ref "J3") (pin "254") (pinfunction "254_254") (pintype "passive+no_connect"))
    )
    (net (code "221") (name "unconnected-(J3-Pad255)") (class "Default")
      (node (ref "J3") (pin "255") (pinfunction "255_255") (pintype "passive+no_connect"))
    )
    (net (code "222") (name "unconnected-(J3-Pad256)") (class "Default")
      (node (ref "J3") (pin "256") (pinfunction "256_256") (pintype "passive+no_connect"))
    )
    (net (code "223") (name "unconnected-(J3-Pad257)") (class "Default")
      (node (ref "J3") (pin "257") (pinfunction "257_257") (pintype "passive+no_connect"))
    )
    (net (code "224") (name "unconnected-(J3-Pad258)") (class "Default")
      (node (ref "J3") (pin "258") (pinfunction "258_258") (pintype "passive+no_connect"))
    )
    (net (code "225") (name "unconnected-(J3-Pad259)") (class "Default")
      (node (ref "J3") (pin "259") (pinfunction "259_259") (pintype "passive+no_connect"))
    )
    (net (code "226") (name "unconnected-(J3-Pad260)") (class "Default")
      (node (ref "J3") (pin "260") (pinfunction "260_260") (pintype "passive+no_connect"))
    )
    (net (code "227") (name "unconnected-(J3-Pad261)") (class "Default")
      (node (ref "J3") (pin "261") (pinfunction "261_261") (pintype "passive+no_connect"))
    )
    (net (code "228") (name "unconnected-(J3-Pad262)") (class "Default")
      (node (ref "J3") (pin "262") (pinfunction "262_262") (pintype "passive+no_connect"))
    )
    (net (code "229") (name "unconnected-(J3-Pad263)") (class "Default")
      (node (ref "J3") (pin "263") (pinfunction "263_263") (pintype "passive+no_connect"))
    )
    (net (code "230") (name "unconnected-(J3-Pad264)") (class "Default")
      (node (ref "J3") (pin "264") (pinfunction "264_264") (pintype "passive+no_connect"))
    )
    (net (code "231") (name "unconnected-(J3-Pad265)") (class "Default")
      (node (ref "J3") (pin "265") (pinfunction "265_265") (pintype "passive+no_connect"))
    )
    (net (code "232") (name "unconnected-(J3-Pad266)") (class "Default")
      (node (ref "J3") (pin "266") (pinfunction "266_266") (pintype "passive+no_connect"))
    )
    (net (code "233") (name "unconnected-(J3-Pad267)") (class "Default")
      (node (ref "J3") (pin "267") (pinfunction "267_267") (pintype "passive+no_connect"))
    )
    (net (code "234") (name "unconnected-(J3-Pad268)") (class "Default")
      (node (ref "J3") (pin "268") (pinfunction "268_268") (pintype "passive+no_connect"))
    )
    (net (code "235") (name "unconnected-(J3-Pad269)") (class "Default")
      (node (ref "J3") (pin "269") (pinfunction "269_269") (pintype "passive+no_connect"))
    )
    (net (code "236") (name "unconnected-(J3-Pad270)") (class "Default")
      (node (ref "J3") (pin "270") (pinfunction "270_270") (pintype "passive+no_connect"))
    )
    (net (code "237") (name "unconnected-(J3-Pad271)") (class "Default")
      (node (ref "J3") (pin "271") (pinfunction "271_271") (pintype "passive+no_connect"))
    )
    (net (code "238") (name "unconnected-(J3-Pad272)") (class "Default")
      (node (ref "J3") (pin "272") (pinfunction "272_272") (pintype "passive+no_connect"))
    )
    (net (code "239") (name "unconnected-(J3-Pad273)") (class "Default")
      (node (ref "J3") (pin "273") (pinfunction "273_273") (pintype "passive+no_connect"))
    )
    (net (code "240") (name "unconnected-(J3-Pad274)") (class "Default")
      (node (ref "J3") (pin "274") (pinfunction "274_274") (pintype "passive+no_connect"))
    )
  )
)
